# CB_v1.net
KiCad netlist of a schematic drawn in EAGLE
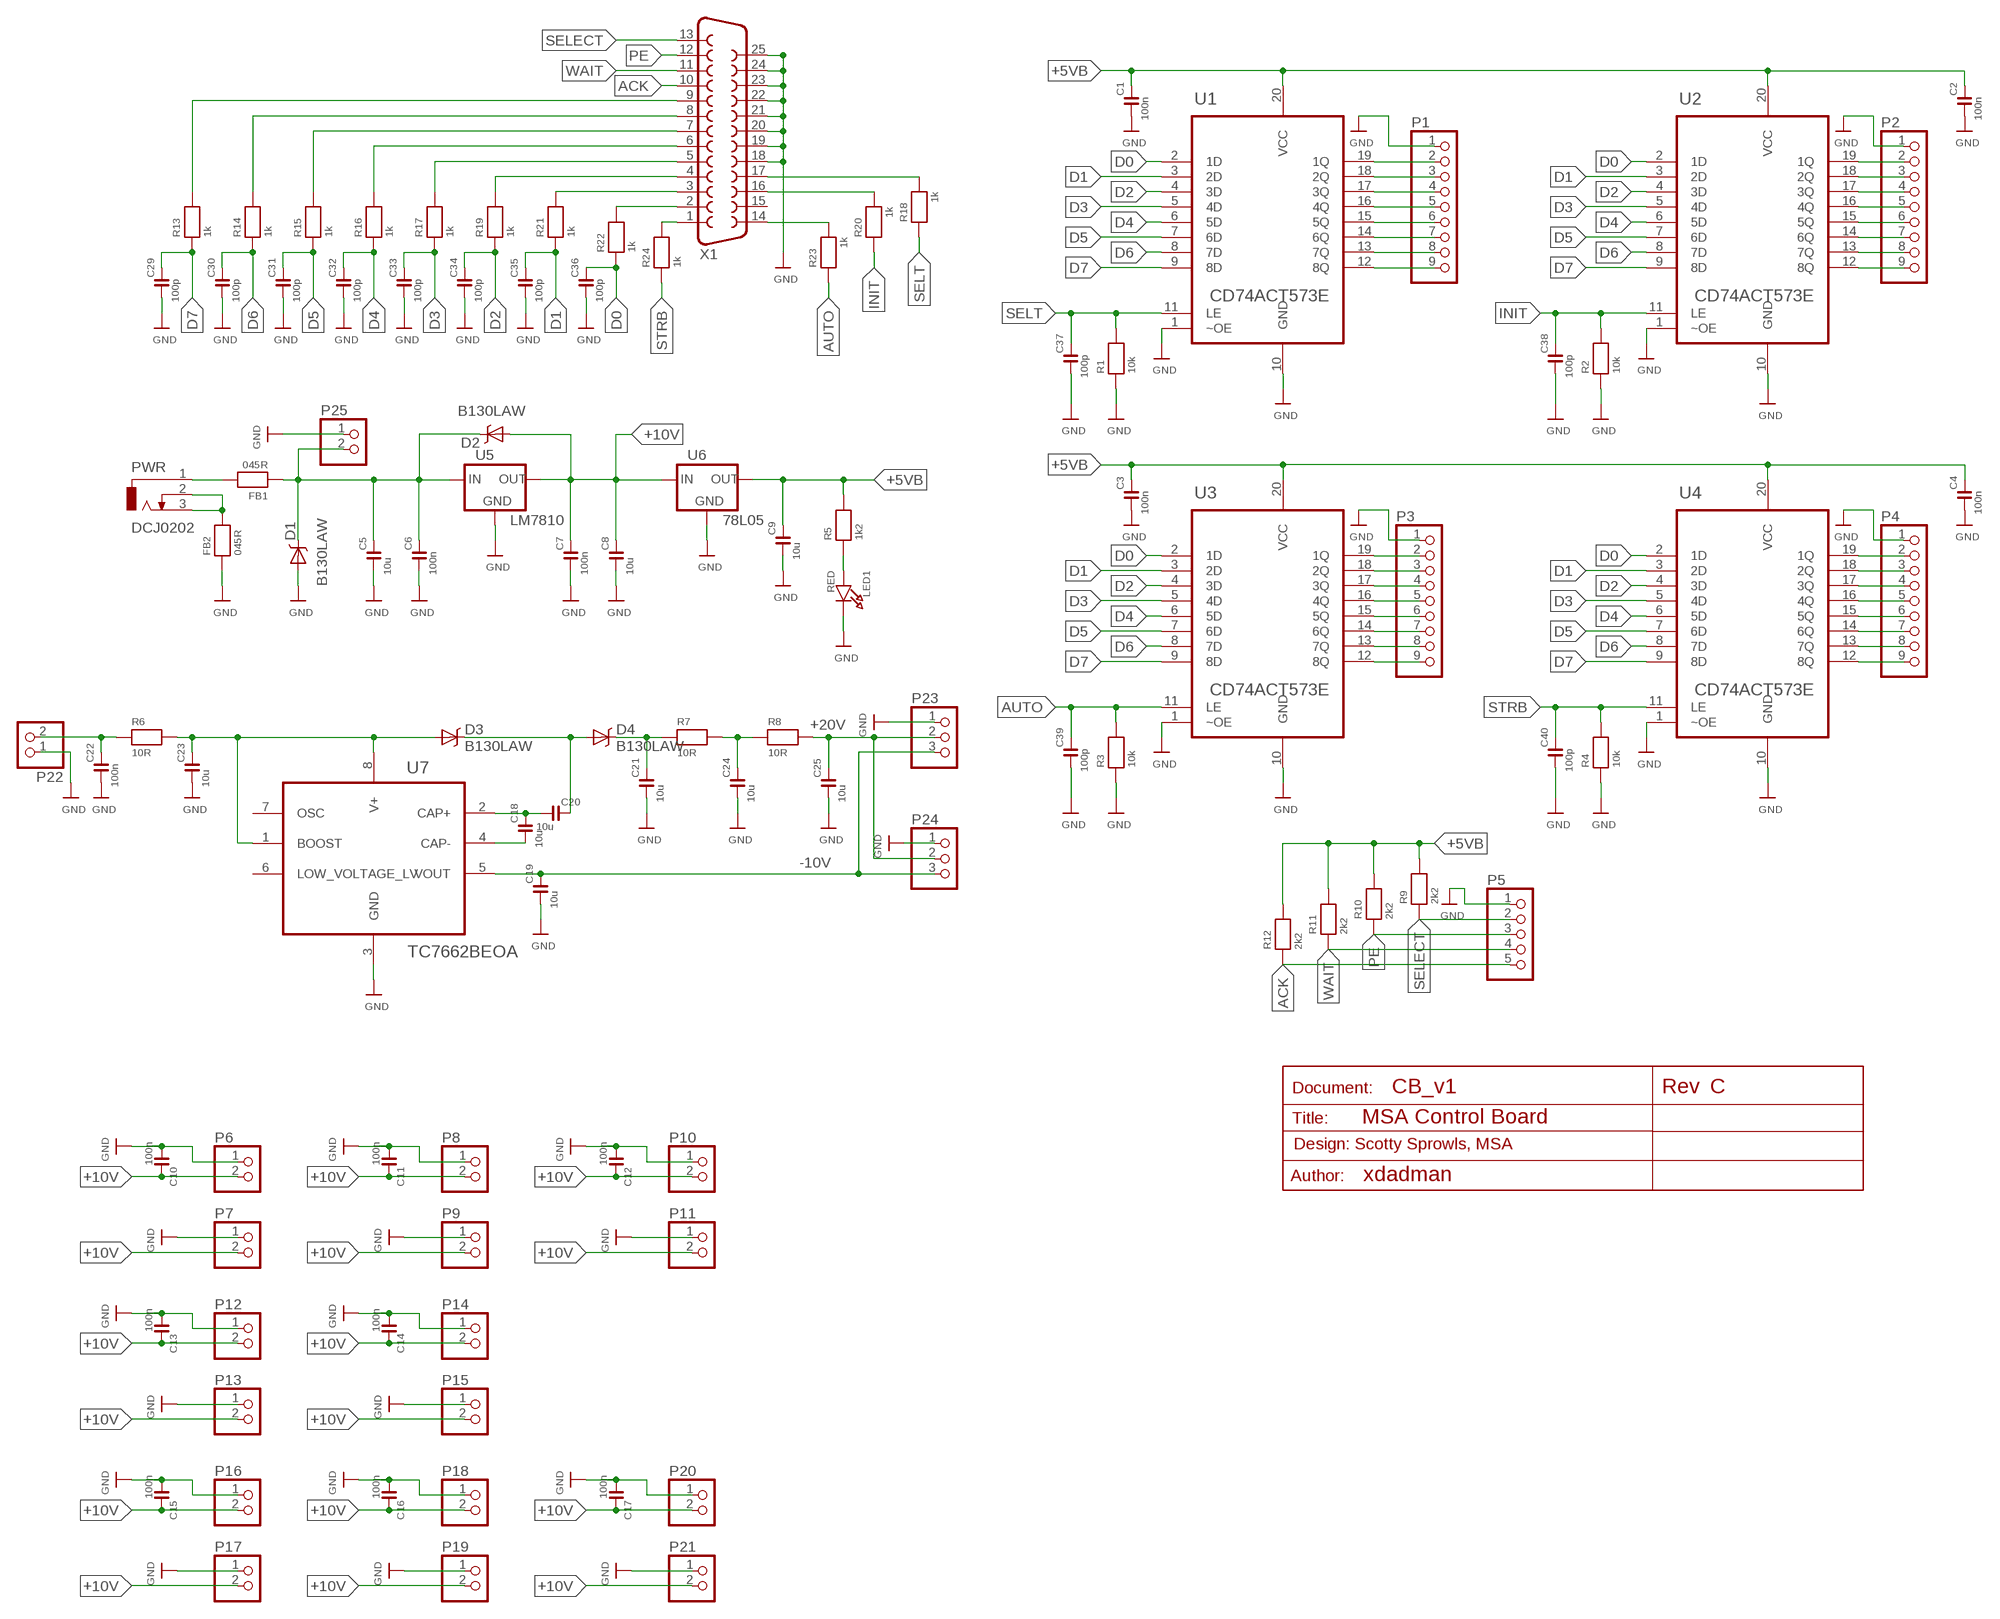
[diagram p0: schematic, sheet 1]

(export (version "E")
  (design (tool "Eeschema 10.0.6"))
  (components
    (comp (ref "C1")
      (value "100n")
      (footprint "eagle-import:C0805")
      (libsource (lib "eagle-import") (part "C0805100N"))
    )
    (comp (ref "C2")
      (value "100n")
      (footprint "eagle-import:C0805")
      (libsource (lib "eagle-import") (part "C0805100N"))
    )
    (comp (ref "C3")
      (value "100n")
      (footprint "eagle-import:C0805")
      (libsource (lib "eagle-import") (part "C0805100N"))
    )
    (comp (ref "C4")
      (value "100n")
      (footprint "eagle-import:C0805")
      (libsource (lib "eagle-import") (part "C0805100N"))
    )
    (comp (ref "C5")
      (value "10u")
      (footprint "eagle-import:C1206")
      (libsource (lib "eagle-import") (part "CC120610U"))
    )
    (comp (ref "C6")
      (value "100n")
      (footprint "eagle-import:C0805")
      (libsource (lib "eagle-import") (part "C0805100N"))
    )
    (comp (ref "C7")
      (value "100n")
      (footprint "eagle-import:C0805")
      (libsource (lib "eagle-import") (part "C0805100N"))
    )
    (comp (ref "C8")
      (value "10u")
      (footprint "eagle-import:C1206")
      (libsource (lib "eagle-import") (part "CC120610U"))
    )
    (comp (ref "C9")
      (value "10u")
      (footprint "eagle-import:C1206")
      (libsource (lib "eagle-import") (part "CC120610U"))
    )
    (comp (ref "C10")
      (value "100n")
      (footprint "eagle-import:C0805")
      (libsource (lib "eagle-import") (part "C0805100N"))
    )
    (comp (ref "C11")
      (value "100n")
      (footprint "eagle-import:C0805")
      (libsource (lib "eagle-import") (part "C0805100N"))
    )
    (comp (ref "C12")
      (value "100n")
      (footprint "eagle-import:C0805")
      (libsource (lib "eagle-import") (part "C0805100N"))
    )
    (comp (ref "C13")
      (value "100n")
      (footprint "eagle-import:C0805")
      (libsource (lib "eagle-import") (part "C0805100N"))
    )
    (comp (ref "C14")
      (value "100n")
      (footprint "eagle-import:C0805")
      (libsource (lib "eagle-import") (part "C0805100N"))
    )
    (comp (ref "C15")
      (value "100n")
      (footprint "eagle-import:C0805")
      (libsource (lib "eagle-import") (part "C0805100N"))
    )
    (comp (ref "C16")
      (value "100n")
      (footprint "eagle-import:C0805")
      (libsource (lib "eagle-import") (part "C0805100N"))
    )
    (comp (ref "C17")
      (value "100n")
      (footprint "eagle-import:C0805")
      (libsource (lib "eagle-import") (part "C0805100N"))
    )
    (comp (ref "C18")
      (value "10u")
      (footprint "eagle-import:C1206")
      (libsource (lib "eagle-import") (part "CC120610U"))
    )
    (comp (ref "C19")
      (value "10u")
      (footprint "eagle-import:C1206")
      (libsource (lib "eagle-import") (part "CC120610U"))
    )
    (comp (ref "C20")
      (value "10u")
      (footprint "eagle-import:C1206")
      (libsource (lib "eagle-import") (part "CC120610U"))
    )
    (comp (ref "C21")
      (value "10u")
      (footprint "eagle-import:C1206")
      (libsource (lib "eagle-import") (part "CC120610U"))
    )
    (comp (ref "C22")
      (value "100n")
      (footprint "eagle-import:C0805")
      (libsource (lib "eagle-import") (part "C0805100N"))
    )
    (comp (ref "C23")
      (value "10u")
      (footprint "eagle-import:C1206")
      (libsource (lib "eagle-import") (part "CC120610U"))
    )
    (comp (ref "C24")
      (value "10u")
      (footprint "eagle-import:C1206")
      (libsource (lib "eagle-import") (part "CC120610U"))
    )
    (comp (ref "C25")
      (value "10u")
      (footprint "eagle-import:C1206")
      (libsource (lib "eagle-import") (part "CC120610U"))
    )
    (comp (ref "C29")
      (value "100p")
      (footprint "eagle-import:C0805")
      (libsource (lib "eagle-import") (part "C0805100P"))
    )
    (comp (ref "C30")
      (value "100p")
      (footprint "eagle-import:C0805")
      (libsource (lib "eagle-import") (part "C0805100P"))
    )
    (comp (ref "C31")
      (value "100p")
      (footprint "eagle-import:C0805")
      (libsource (lib "eagle-import") (part "C0805100P"))
    )
    (comp (ref "C32")
      (value "100p")
      (footprint "eagle-import:C0805")
      (libsource (lib "eagle-import") (part "C0805100P"))
    )
    (comp (ref "C33")
      (value "100p")
      (footprint "eagle-import:C0805")
      (libsource (lib "eagle-import") (part "C0805100P"))
    )
    (comp (ref "C34")
      (value "100p")
      (footprint "eagle-import:C0805")
      (libsource (lib "eagle-import") (part "C0805100P"))
    )
    (comp (ref "C35")
      (value "100p")
      (footprint "eagle-import:C0805")
      (libsource (lib "eagle-import") (part "C0805100P"))
    )
    (comp (ref "C36")
      (value "100p")
      (footprint "eagle-import:C0805")
      (libsource (lib "eagle-import") (part "C0805100P"))
    )
    (comp (ref "C37")
      (value "100p")
      (footprint "eagle-import:C0805")
      (libsource (lib "eagle-import") (part "C0805100P"))
    )
    (comp (ref "C38")
      (value "100p")
      (footprint "eagle-import:C0805")
      (libsource (lib "eagle-import") (part "C0805100P"))
    )
    (comp (ref "C39")
      (value "100p")
      (footprint "eagle-import:C0805")
      (libsource (lib "eagle-import") (part "C0805100P"))
    )
    (comp (ref "C40")
      (value "100p")
      (footprint "eagle-import:C0805")
      (libsource (lib "eagle-import") (part "C0805100P"))
    )
    (comp (ref "D1")
      (value "B130LAW")
      (footprint "eagle-import:SOD-123")
      (libsource (lib "eagle-import") (part "B130LAW-7-FB130LAW-7-F"))
    )
    (comp (ref "D2")
      (value "B130LAW")
      (footprint "eagle-import:SOD-123")
      (libsource (lib "eagle-import") (part "B130LAW-7-FB130LAW-7-F"))
    )
    (comp (ref "D3")
      (value "B130LAW")
      (footprint "eagle-import:SOD-123")
      (libsource (lib "eagle-import") (part "B130LAW-7-FB130LAW-7-F"))
    )
    (comp (ref "D4")
      (value "B130LAW")
      (footprint "eagle-import:SOD-123")
      (libsource (lib "eagle-import") (part "B130LAW-7-FB130LAW-7-F"))
    )
    (comp (ref "FB1")
      (value "045R")
      (footprint "eagle-import:R0805")
      (libsource (lib "eagle-import") (part "R0805FB045"))
    )
    (comp (ref "FB2")
      (value "045R")
      (footprint "eagle-import:R0805")
      (libsource (lib "eagle-import") (part "R0805FB045"))
    )
    (comp (ref "LED1")
      (value "RED")
      (footprint "eagle-import:CHIPLED_0603")
      (libsource (lib "eagle-import") (part "LED_0603_RED0603"))
    )
    (comp (ref "P1")
      (value "PINHD-1X9")
      (footprint "eagle-import:1X09ROUND")
      (libsource (lib "eagle-import") (part "PINHD-1X9"))
    )
    (comp (ref "P2")
      (value "PINHD-1X9")
      (footprint "eagle-import:1X09ROUND")
      (libsource (lib "eagle-import") (part "PINHD-1X9"))
    )
    (comp (ref "P3")
      (value "PINHD-1X9")
      (footprint "eagle-import:1X09ROUND")
      (libsource (lib "eagle-import") (part "PINHD-1X9"))
    )
    (comp (ref "P4")
      (value "PINHD-1X9")
      (footprint "eagle-import:1X09ROUND")
      (libsource (lib "eagle-import") (part "PINHD-1X9"))
    )
    (comp (ref "P5")
      (value "PINHD-1X5")
      (footprint "eagle-import:1X05")
      (libsource (lib "eagle-import") (part "PINHD-1X5"))
    )
    (comp (ref "P6")
      (value "PINHD-1X2")
      (footprint "eagle-import:1X02")
      (libsource (lib "eagle-import") (part "PINHD-1X2"))
    )
    (comp (ref "P7")
      (value "PINHD-1X2")
      (footprint "eagle-import:1X02")
      (libsource (lib "eagle-import") (part "PINHD-1X2"))
    )
    (comp (ref "P8")
      (value "PINHD-1X2")
      (footprint "eagle-import:1X02")
      (libsource (lib "eagle-import") (part "PINHD-1X2"))
    )
    (comp (ref "P9")
      (value "PINHD-1X2")
      (footprint "eagle-import:1X02")
      (libsource (lib "eagle-import") (part "PINHD-1X2"))
    )
    (comp (ref "P10")
      (value "PINHD-1X2")
      (footprint "eagle-import:1X02")
      (libsource (lib "eagle-import") (part "PINHD-1X2"))
    )
    (comp (ref "P11")
      (value "PINHD-1X2")
      (footprint "eagle-import:1X02")
      (libsource (lib "eagle-import") (part "PINHD-1X2"))
    )
    (comp (ref "P12")
      (value "PINHD-1X2")
      (footprint "eagle-import:1X02")
      (libsource (lib "eagle-import") (part "PINHD-1X2"))
    )
    (comp (ref "P13")
      (value "PINHD-1X2")
      (footprint "eagle-import:1X02")
      (libsource (lib "eagle-import") (part "PINHD-1X2"))
    )
    (comp (ref "P14")
      (value "PINHD-1X2")
      (footprint "eagle-import:1X02")
      (libsource (lib "eagle-import") (part "PINHD-1X2"))
    )
    (comp (ref "P15")
      (value "PINHD-1X2")
      (footprint "eagle-import:1X02")
      (libsource (lib "eagle-import") (part "PINHD-1X2"))
    )
    (comp (ref "P16")
      (value "PINHD-1X2")
      (footprint "eagle-import:1X02")
      (libsource (lib "eagle-import") (part "PINHD-1X2"))
    )
    (comp (ref "P17")
      (value "PINHD-1X2")
      (footprint "eagle-import:1X02")
      (libsource (lib "eagle-import") (part "PINHD-1X2"))
    )
    (comp (ref "P18")
      (value "PINHD-1X2")
      (footprint "eagle-import:1X02")
      (libsource (lib "eagle-import") (part "PINHD-1X2"))
    )
    (comp (ref "P19")
      (value "PINHD-1X2")
      (footprint "eagle-import:1X02")
      (libsource (lib "eagle-import") (part "PINHD-1X2"))
    )
    (comp (ref "P20")
      (value "PINHD-1X2")
      (footprint "eagle-import:1X02")
      (libsource (lib "eagle-import") (part "PINHD-1X2"))
    )
    (comp (ref "P21")
      (value "PINHD-1X2")
      (footprint "eagle-import:1X02")
      (libsource (lib "eagle-import") (part "PINHD-1X2"))
    )
    (comp (ref "P22")
      (value "PINHD-1X2")
      (footprint "eagle-import:1X02")
      (libsource (lib "eagle-import") (part "PINHD-1X2"))
    )
    (comp (ref "P23")
      (value "PINHD-1X3")
      (footprint "eagle-import:1X03")
      (libsource (lib "eagle-import") (part "PINHD-1X3"))
    )
    (comp (ref "P24")
      (value "PINHD-1X3")
      (footprint "eagle-import:1X03")
      (libsource (lib "eagle-import") (part "PINHD-1X3"))
    )
    (comp (ref "P25")
      (value "PINHD-1X2")
      (footprint "eagle-import:1X02")
      (libsource (lib "eagle-import") (part "PINHD-1X2"))
    )
    (comp (ref "PWR")
      (value "DCJ0202")
      (footprint "eagle-import:DCJ0202")
      (libsource (lib "eagle-import") (part "DCJ0202"))
    )
    (comp (ref "R1")
      (value "10k")
      (footprint "eagle-import:R0805")
      (libsource (lib "eagle-import") (part "R080510K"))
    )
    (comp (ref "R2")
      (value "10k")
      (footprint "eagle-import:R0805")
      (libsource (lib "eagle-import") (part "R080510K"))
    )
    (comp (ref "R3")
      (value "10k")
      (footprint "eagle-import:R0805")
      (libsource (lib "eagle-import") (part "R080510K"))
    )
    (comp (ref "R4")
      (value "10k")
      (footprint "eagle-import:R0805")
      (libsource (lib "eagle-import") (part "R080510K"))
    )
    (comp (ref "R5")
      (value "1k2")
      (footprint "eagle-import:R0805")
      (libsource (lib "eagle-import") (part "R08051K2"))
    )
    (comp (ref "R6")
      (value "10R")
      (footprint "eagle-import:R0805")
      (libsource (lib "eagle-import") (part "R080510R"))
    )
    (comp (ref "R7")
      (value "10R")
      (footprint "eagle-import:R0805")
      (libsource (lib "eagle-import") (part "R080510R"))
    )
    (comp (ref "R8")
      (value "10R")
      (footprint "eagle-import:R0805")
      (libsource (lib "eagle-import") (part "R080510R"))
    )
    (comp (ref "R9")
      (value "2k2")
      (footprint "eagle-import:R0805")
      (libsource (lib "eagle-import") (part "R08052K2"))
    )
    (comp (ref "R10")
      (value "2k2")
      (footprint "eagle-import:R0805")
      (libsource (lib "eagle-import") (part "R08052K2"))
    )
    (comp (ref "R11")
      (value "2k2")
      (footprint "eagle-import:R0805")
      (libsource (lib "eagle-import") (part "R08052K2"))
    )
    (comp (ref "R12")
      (value "2k2")
      (footprint "eagle-import:R0805")
      (libsource (lib "eagle-import") (part "R08052K2"))
    )
    (comp (ref "R13")
      (value "1k")
      (footprint "eagle-import:R0805")
      (libsource (lib "eagle-import") (part "R08051K"))
    )
    (comp (ref "R14")
      (value "1k")
      (footprint "eagle-import:R0805")
      (libsource (lib "eagle-import") (part "R08051K"))
    )
    (comp (ref "R15")
      (value "1k")
      (footprint "eagle-import:R0805")
      (libsource (lib "eagle-import") (part "R08051K"))
    )
    (comp (ref "R16")
      (value "1k")
      (footprint "eagle-import:R0805")
      (libsource (lib "eagle-import") (part "R08051K"))
    )
    (comp (ref "R17")
      (value "1k")
      (footprint "eagle-import:R0805")
      (libsource (lib "eagle-import") (part "R08051K"))
    )
    (comp (ref "R18")
      (value "1k")
      (footprint "eagle-import:R0805")
      (libsource (lib "eagle-import") (part "R08051K"))
    )
    (comp (ref "R19")
      (value "1k")
      (footprint "eagle-import:R0805")
      (libsource (lib "eagle-import") (part "R08051K"))
    )
    (comp (ref "R20")
      (value "1k")
      (footprint "eagle-import:R0805")
      (libsource (lib "eagle-import") (part "R08051K"))
    )
    (comp (ref "R21")
      (value "1k")
      (footprint "eagle-import:R0805")
      (libsource (lib "eagle-import") (part "R08051K"))
    )
    (comp (ref "R22")
      (value "1k")
      (footprint "eagle-import:R0805")
      (libsource (lib "eagle-import") (part "R08051K"))
    )
    (comp (ref "R23")
      (value "1k")
      (footprint "eagle-import:R0805")
      (libsource (lib "eagle-import") (part "R08051K"))
    )
    (comp (ref "R24")
      (value "1k")
      (footprint "eagle-import:R0805")
      (libsource (lib "eagle-import") (part "R08051K"))
    )
    (comp (ref "U1")
      (value "CD74ACT573E")
      (footprint "eagle-import:DIP254P762X508-20")
      (libsource (lib "eagle-import") (part "CD74ACT573E"))
    )
    (comp (ref "U2")
      (value "CD74ACT573E")
      (footprint "eagle-import:DIP254P762X508-20")
      (libsource (lib "eagle-import") (part "CD74ACT573E"))
    )
    (comp (ref "U3")
      (value "CD74ACT573E")
      (footprint "eagle-import:DIP254P762X508-20")
      (libsource (lib "eagle-import") (part "CD74ACT573E"))
    )
    (comp (ref "U4")
      (value "CD74ACT573E")
      (footprint "eagle-import:DIP254P762X508-20")
      (libsource (lib "eagle-import") (part "CD74ACT573E"))
    )
    (comp (ref "U5")
      (value "LM7810")
      (footprint "eagle-import:TO220V")
      (libsource (lib "eagle-import") (part "78MXXLLM7810"))
    )
    (comp (ref "U6")
      (value "78L05")
      (footprint "eagle-import:SOT89")
      (libsource (lib "eagle-import") (part "78MXXL78L05"))
    )
    (comp (ref "U7")
      (value "TC7662BEOA")
      (footprint "eagle-import:SOIC127P600X175-8N_JDA")
      (libsource (lib "eagle-import") (part "TC7662BEOA"))
    )
    (comp (ref "X1")
      (value "F25D")
      (footprint "eagle-import:F25D")
      (libsource (lib "eagle-import") (part "F25D"))
    )
  )
  (nets
    (net (code "1") (name "+5VB") (class "Default")
      (node (ref "C1") (pin "2") (pinfunction "2_2") (pintype "passive"))
      (node (ref "C2") (pin "2") (pinfunction "2_2") (pintype "passive"))
      (node (ref "C3") (pin "2") (pinfunction "2_2") (pintype "passive"))
      (node (ref "C4") (pin "2") (pinfunction "2_2") (pintype "passive"))
      (node (ref "C9") (pin "2") (pinfunction "2_2") (pintype "passive"))
      (node (ref "R10") (pin "2") (pinfunction "2_2") (pintype "passive"))
      (node (ref "R11") (pin "2") (pinfunction "2_2") (pintype "passive"))
      (node (ref "R12") (pin "2") (pinfunction "2_2") (pintype "passive"))
      (node (ref "R5") (pin "2") (pinfunction "2_2") (pintype "passive"))
      (node (ref "R9") (pin "2") (pinfunction "2_2") (pintype "passive"))
      (node (ref "U1") (pin "20") (pinfunction "VCC_20") (pintype "power_in"))
      (node (ref "U2") (pin "20") (pinfunction "VCC_20") (pintype "power_in"))
      (node (ref "U3") (pin "20") (pinfunction "VCC_20") (pintype "power_in"))
      (node (ref "U4") (pin "20") (pinfunction "VCC_20") (pintype "power_in"))
      (node (ref "U6") (pin "1") (pinfunction "OUT_1") (pintype "passive"))
    )
    (net (code "2") (name "+10V") (class "Default")
      (node (ref "C10") (pin "2") (pinfunction "2_2") (pintype "passive"))
      (node (ref "C11") (pin "2") (pinfunction "2_2") (pintype "passive"))
      (node (ref "C12") (pin "2") (pinfunction "2_2") (pintype "passive"))
      (node (ref "C13") (pin "2") (pinfunction "2_2") (pintype "passive"))
      (node (ref "C14") (pin "2") (pinfunction "2_2") (pintype "passive"))
      (node (ref "C15") (pin "2") (pinfunction "2_2") (pintype "passive"))
      (node (ref "C16") (pin "2") (pinfunction "2_2") (pintype "passive"))
      (node (ref "C17") (pin "2") (pinfunction "2_2") (pintype "passive"))
      (node (ref "C7") (pin "2") (pinfunction "2_2") (pintype "passive"))
      (node (ref "C8") (pin "2") (pinfunction "2_2") (pintype "passive"))
      (node (ref "D2") (pin "A") (pinfunction "A_A") (pintype "passive"))
      (node (ref "P10") (pin "2") (pinfunction "2_2") (pintype "passive"))
      (node (ref "P11") (pin "2") (pinfunction "2_2") (pintype "passive"))
      (node (ref "P12") (pin "2") (pinfunction "2_2") (pintype "passive"))
      (node (ref "P13") (pin "2") (pinfunction "2_2") (pintype "passive"))
      (node (ref "P14") (pin "2") (pinfunction "2_2") (pintype "passive"))
      (node (ref "P15") (pin "2") (pinfunction "2_2") (pintype "passive"))
      (node (ref "P16") (pin "2") (pinfunction "2_2") (pintype "passive"))
      (node (ref "P17") (pin "2") (pinfunction "2_2") (pintype "passive"))
      (node (ref "P18") (pin "2") (pinfunction "2_2") (pintype "passive"))
      (node (ref "P19") (pin "2") (pinfunction "2_2") (pintype "passive"))
      (node (ref "P20") (pin "2") (pinfunction "2_2") (pintype "passive"))
      (node (ref "P21") (pin "2") (pinfunction "2_2") (pintype "passive"))
      (node (ref "P6") (pin "2") (pinfunction "2_2") (pintype "passive"))
      (node (ref "P7") (pin "2") (pinfunction "2_2") (pintype "passive"))
      (node (ref "P8") (pin "2") (pinfunction "2_2") (pintype "passive"))
      (node (ref "P9") (pin "2") (pinfunction "2_2") (pintype "passive"))
      (node (ref "U5") (pin "3") (pinfunction "OUT_3") (pintype "passive"))
      (node (ref "U6") (pin "3") (pinfunction "IN_3") (pintype "input"))
    )
    (net (code "3") (name "/+20V") (class "Default")
      (node (ref "C25") (pin "2") (pinfunction "2_2") (pintype "passive"))
      (node (ref "P23") (pin "2") (pinfunction "2_2") (pintype "passive"))
      (node (ref "P24") (pin "2") (pinfunction "2_2") (pintype "passive"))
      (node (ref "R8") (pin "2") (pinfunction "2_2") (pintype "passive"))
    )
    (net (code "4") (name "/-10V") (class "Default")
      (node (ref "C19") (pin "2") (pinfunction "2_2") (pintype "passive"))
      (node (ref "P23") (pin "3") (pinfunction "3_3") (pintype "passive"))
      (node (ref "P24") (pin "3") (pinfunction "3_3") (pintype "passive"))
      (node (ref "U7") (pin "5") (pinfunction "VOUT_5") (pintype "output"))
    )
    (net (code "5") (name "ACK") (class "Default")
      (node (ref "P5") (pin "5") (pinfunction "5_5") (pintype "passive"))
      (node (ref "R12") (pin "1") (pinfunction "1_1") (pintype "passive"))
      (node (ref "X1") (pin "10") (pinfunction "10_10") (pintype "passive"))
    )
    (net (code "6") (name "AUTO") (class "Default")
      (node (ref "C39") (pin "2") (pinfunction "2_2") (pintype "passive"))
      (node (ref "R23") (pin "2") (pinfunction "2_2") (pintype "passive"))
      (node (ref "R3") (pin "2") (pinfunction "2_2") (pintype "passive"))
      (node (ref "U3") (pin "11") (pinfunction "LE_11") (pintype "input"))
    )
    (net (code "7") (name "D0") (class "Default")
      (node (ref "C36") (pin "2") (pinfunction "2_2") (pintype "passive"))
      (node (ref "R22") (pin "1") (pinfunction "1_1") (pintype "passive"))
      (node (ref "U1") (pin "2") (pinfunction "1D_2") (pintype "input"))
      (node (ref "U2") (pin "2") (pinfunction "1D_2") (pintype "input"))
      (node (ref "U3") (pin "2") (pinfunction "1D_2") (pintype "input"))
      (node (ref "U4") (pin "2") (pinfunction "1D_2") (pintype "input"))
    )
    (net (code "8") (name "D1") (class "Default")
      (node (ref "C35") (pin "2") (pinfunction "2_2") (pintype "passive"))
      (node (ref "R21") (pin "1") (pinfunction "1_1") (pintype "passive"))
      (node (ref "U1") (pin "3") (pinfunction "2D_3") (pintype "input"))
      (node (ref "U2") (pin "3") (pinfunction "2D_3") (pintype "input"))
      (node (ref "U3") (pin "3") (pinfunction "2D_3") (pintype "input"))
      (node (ref "U4") (pin "3") (pinfunction "2D_3") (pintype "input"))
    )
    (net (code "9") (name "D2") (class "Default")
      (node (ref "C34") (pin "2") (pinfunction "2_2") (pintype "passive"))
      (node (ref "R19") (pin "1") (pinfunction "1_1") (pintype "passive"))
      (node (ref "U1") (pin "4") (pinfunction "3D_4") (pintype "input"))
      (node (ref "U2") (pin "4") (pinfunction "3D_4") (pintype "input"))
      (node (ref "U3") (pin "4") (pinfunction "3D_4") (pintype "input"))
      (node (ref "U4") (pin "4") (pinfunction "3D_4") (pintype "input"))
    )
    (net (code "10") (name "D3") (class "Default")
      (node (ref "C33") (pin "2") (pinfunction "2_2") (pintype "passive"))
      (node (ref "R17") (pin "1") (pinfunction "1_1") (pintype "passive"))
      (node (ref "U1") (pin "5") (pinfunction "4D_5") (pintype "input"))
      (node (ref "U2") (pin "5") (pinfunction "4D_5") (pintype "input"))
      (node (ref "U3") (pin "5") (pinfunction "4D_5") (pintype "input"))
      (node (ref "U4") (pin "5") (pinfunction "4D_5") (pintype "input"))
    )
    (net (code "11") (name "D4") (class "Default")
      (node (ref "C32") (pin "2") (pinfunction "2_2") (pintype "passive"))
      (node (ref "R16") (pin "1") (pinfunction "1_1") (pintype "passive"))
      (node (ref "U1") (pin "6") (pinfunction "5D_6") (pintype "input"))
      (node (ref "U2") (pin "6") (pinfunction "5D_6") (pintype "input"))
      (node (ref "U3") (pin "6") (pinfunction "5D_6") (pintype "input"))
      (node (ref "U4") (pin "6") (pinfunction "5D_6") (pintype "input"))
    )
    (net (code "12") (name "D5") (class "Default")
      (node (ref "C31") (pin "2") (pinfunction "2_2") (pintype "passive"))
      (node (ref "R15") (pin "1") (pinfunction "1_1") (pintype "passive"))
      (node (ref "U1") (pin "7") (pinfunction "6D_7") (pintype "input"))
      (node (ref "U2") (pin "7") (pinfunction "6D_7") (pintype "input"))
      (node (ref "U3") (pin "7") (pinfunction "6D_7") (pintype "input"))
      (node (ref "U4") (pin "7") (pinfunction "6D_7") (pintype "input"))
    )
    (net (code "13") (name "D6") (class "Default")
      (node (ref "C30") (pin "2") (pinfunction "2_2") (pintype "passive"))
      (node (ref "R14") (pin "1") (pinfunction "1_1") (pintype "passive"))
      (node (ref "U1") (pin "8") (pinfunction "7D_8") (pintype "input"))
      (node (ref "U2") (pin "8") (pinfunction "7D_8") (pintype "input"))
      (node (ref "U3") (pin "8") (pinfunction "7D_8") (pintype "input"))
      (node (ref "U4") (pin "8") (pinfunction "7D_8") (pintype "input"))
    )
    (net (code "14") (name "D7") (class "Default")
      (node (ref "C29") (pin "2") (pinfunction "2_2") (pintype "passive"))
      (node (ref "R13") (pin "1") (pinfunction "1_1") (pintype "passive"))
      (node (ref "U1") (pin "9") (pinfunction "8D_9") (pintype "input"))
      (node (ref "U2") (pin "9") (pinfunction "8D_9") (pintype "input"))
      (node (ref "U3") (pin "9") (pinfunction "8D_9") (pintype "input"))
      (node (ref "U4") (pin "9") (pinfunction "8D_9") (pintype "input"))
    )
    (net (code "15") (name "GND") (class "Default")
      (node (ref "C1") (pin "1") (pinfunction "1_1") (pintype "passive"))
      (node (ref "C10") (pin "1") (pinfunction "1_1") (pintype "passive"))
      (node (ref "C11") (pin "1") (pinfunction "1_1") (pintype "passive"))
      (node (ref "C12") (pin "1") (pinfunction "1_1") (pintype "passive"))
      (node (ref "C13") (pin "1") (pinfunction "1_1") (pintype "passive"))
      (node (ref "C14") (pin "1") (pinfunction "1_1") (pintype "passive"))
      (node (ref "C15") (pin "1") (pinfunction "1_1") (pintype "passive"))
      (node (ref "C16") (pin "1") (pinfunction "1_1") (pintype "passive"))
      (node (ref "C17") (pin "1") (pinfunction "1_1") (pintype "passive"))
      (node (ref "C19") (pin "1") (pinfunction "1_1") (pintype "passive"))
      (node (ref "C2") (pin "1") (pinfunction "1_1") (pintype "passive"))
      (node (ref "C21") (pin "1") (pinfunction "1_1") (pintype "passive"))
      (node (ref "C22") (pin "1") (pinfunction "1_1") (pintype "passive"))
      (node (ref "C23") (pin "1") (pinfunction "1_1") (pintype "passive"))
      (node (ref "C24") (pin "1") (pinfunction "1_1") (pintype "passive"))
      (node (ref "C25") (pin "1") (pinfunction "1_1") (pintype "passive"))
      (node (ref "C29") (pin "1") (pinfunction "1_1") (pintype "passive"))
      (node (ref "C3") (pin "1") (pinfunction "1_1") (pintype "passive"))
      (node (ref "C30") (pin "1") (pinfunction "1_1") (pintype "passive"))
      (node (ref "C31") (pin "1") (pinfunction "1_1") (pintype "passive"))
      (node (ref "C32") (pin "1") (pinfunction "1_1") (pintype "passive"))
      (node (ref "C33") (pin "1") (pinfunction "1_1") (pintype "passive"))
      (node (ref "C34") (pin "1") (pinfunction "1_1") (pintype "passive"))
      (node (ref "C35") (pin "1") (pinfunction "1_1") (pintype "passive"))
      (node (ref "C36") (pin "1") (pinfunction "1_1") (pintype "passive"))
      (node (ref "C37") (pin "1") (pinfunction "1_1") (pintype "passive"))
      (node (ref "C38") (pin "1") (pinfunction "1_1") (pintype "passive"))
      (node (ref "C39") (pin "1") (pinfunction "1_1") (pintype "passive"))
      (node (ref "C4") (pin "1") (pinfunction "1_1") (pintype "passive"))
      (node (ref "C40") (pin "1") (pinfunction "1_1") (pintype "passive"))
      (node (ref "C5") (pin "1") (pinfunction "1_1") (pintype "passive"))
      (node (ref "C6") (pin "1") (pinfunction "1_1") (pintype "passive"))
      (node (ref "C7") (pin "1") (pinfunction "1_1") (pintype "passive"))
      (node (ref "C8") (pin "1") (pinfunction "1_1") (pintype "passive"))
      (node (ref "C9") (pin "1") (pinfunction "1_1") (pintype "passive"))
      (node (ref "D1") (pin "A") (pinfunction "A_A") (pintype "passive"))
      (node (ref "FB2") (pin "1") (pinfunction "1_1") (pintype "passive"))
      (node (ref "LED1") (pin "C") (pinfunction "C_C") (pintype "passive"))
      (node (ref "P1") (pin "1") (pinfunction "1_1") (pintype "passive"))
      (node (ref "P10") (pin "1") (pinfunction "1_1") (pintype "passive"))
      (node (ref "P11") (pin "1") (pinfunction "1_1") (pintype "passive"))
      (node (ref "P12") (pin "1") (pinfunction "1_1") (pintype "passive"))
      (node (ref "P13") (pin "1") (pinfunction "1_1") (pintype "passive"))
      (node (ref "P14") (pin "1") (pinfunction "1_1") (pintype "passive"))
      (node (ref "P15") (pin "1") (pinfunction "1_1") (pintype "passive"))
      (node (ref "P16") (pin "1") (pinfunction "1_1") (pintype "passive"))
      (node (ref "P17") (pin "1") (pinfunction "1_1") (pintype "passive"))
      (node (ref "P18") (pin "1") (pinfunction "1_1") (pintype "passive"))
      (node (ref "P19") (pin "1") (pinfunction "1_1") (pintype "passive"))
      (node (ref "P2") (pin "1") (pinfunction "1_1") (pintype "passive"))
      (node (ref "P20") (pin "1") (pinfunction "1_1") (pintype "passive"))
      (node (ref "P21") (pin "1") (pinfunction "1_1") (pintype "passive"))
      (node (ref "P22") (pin "1") (pinfunction "1_1") (pintype "passive"))
      (node (ref "P23") (pin "1") (pinfunction "1_1") (pintype "passive"))
      (node (ref "P24") (pin "1") (pinfunction "1_1") (pintype "passive"))
      (node (ref "P25") (pin "1") (pinfunction "1_1") (pintype "passive"))
      (node (ref "P3") (pin "1") (pinfunction "1_1") (pintype "passive"))
      (node (ref "P4") (pin "1") (pinfunction "1_1") (pintype "passive"))
      (node (ref "P5") (pin "1") (pinfunction "1_1") (pintype "passive"))
      (node (ref "P6") (pin "1") (pinfunction "1_1") (pintype "passive"))
      (node (ref "P7") (pin "1") (pinfunction "1_1") (pintype "passive"))
      (node (ref "P8") (pin "1") (pinfunction "1_1") (pintype "passive"))
      (node (ref "P9") (pin "1") (pinfunction "1_1") (pintype "passive"))
      (node (ref "R1") (pin "1") (pinfunction "1_1") (pintype "passive"))
      (node (ref "R2") (pin "1") (pinfunction "1_1") (pintype "passive"))
      (node (ref "R3") (pin "1") (pinfunction "1_1") (pintype "passive"))
      (node (ref "R4") (pin "1") (pinfunction "1_1") (pintype "passive"))
      (node (ref "U1") (pin "1") (pinfunction "~{OE}_1") (pintype "input"))
      (node (ref "U1") (pin "10") (pinfunction "GND_10") (pintype "passive"))
      (node (ref "U2") (pin "1") (pinfunction "~{OE}_1") (pintype "input"))
      (node (ref "U2") (pin "10") (pinfunction "GND_10") (pintype "passive"))
      (node (ref "U3") (pin "1") (pinfunction "~{OE}_1") (pintype "input"))
      (node (ref "U3") (pin "10") (pinfunction "GND_10") (pintype "passive"))
      (node (ref "U4") (pin "1") (pinfunction "~{OE}_1") (pintype "input"))
      (node (ref "U4") (pin "10") (pinfunction "GND_10") (pintype "passive"))
      (node (ref "U5") (pin "2") (pinfunction "GND_2") (pintype "input"))
      (node (ref "U6") (pin "2") (pinfunction "GND_2") (pintype "input"))
      (node (ref "U6") (pin "4") (pinfunction "GND_4") (pintype "input"))
      (node (ref "U7") (pin "3") (pinfunction "GND_3") (pintype "passive"))
      (node (ref "X1") (pin "18") (pinfunction "18_18") (pintype "passive"))
      (node (ref "X1") (pin "19") (pinfunction "19_19") (pintype "passive"))
      (node (ref "X1") (pin "20") (pinfunction "20_20") (pintype "passive"))
      (node (ref "X1") (pin "21") (pinfunction "21_21") (pintype "passive"))
      (node (ref "X1") (pin "22") (pinfunction "22_22") (pintype "passive"))
      (node (ref "X1") (pin "23") (pinfunction "23_23") (pintype "passive"))
      (node (ref "X1") (pin "24") (pinfunction "24_24") (pintype "passive"))
      (node (ref "X1") (pin "25") (pinfunction "25_25") (pintype "passive"))
    )
    (net (code "16") (name "INIT") (class "Default")
      (node (ref "C38") (pin "2") (pinfunction "2_2") (pintype "passive"))
      (node (ref "R2") (pin "2") (pinfunction "2_2") (pintype "passive"))
      (node (ref "R20") (pin "2") (pinfunction "2_2") (pintype "passive"))
      (node (ref "U2") (pin "11") (pinfunction "LE_11") (pintype "input"))
    )
    (net (code "17") (name "Net-(C20-Pad2)") (class "Default")
      (node (ref "C20") (pin "2") (pinfunction "2_2") (pintype "passive"))
      (node (ref "D3") (pin "C") (pinfunction "C_C") (pintype "passive"))
      (node (ref "D4") (pin "A") (pinfunction "A_A") (pintype "passive"))
    )
    (net (code "18") (name "Net-(C21-Pad2)") (class "Default")
      (node (ref "C21") (pin "2") (pinfunction "2_2") (pintype "passive"))
      (node (ref "D4") (pin "C") (pinfunction "C_C") (pintype "passive"))
      (node (ref "R7") (pin "1") (pinfunction "1_1") (pintype "passive"))
    )
    (net (code "19") (name "Net-(C22-Pad2)") (class "Default")
      (node (ref "C22") (pin "2") (pinfunction "2_2") (pintype "passive"))
      (node (ref "P22") (pin "2") (pinfunction "2_2") (pintype "passive"))
      (node (ref "R6") (pin "1") (pinfunction "1_1") (pintype "passive"))
    )
    (net (code "20") (name "Net-(C24-Pad2)") (class "Default")
      (node (ref "C24") (pin "2") (pinfunction "2_2") (pintype "passive"))
      (node (ref "R7") (pin "2") (pinfunction "2_2") (pintype "passive"))
      (node (ref "R8") (pin "1") (pinfunction "1_1") (pintype "passive"))
    )
    (net (code "21") (name "Net-(FB1-Pad2)") (class "Default")
      (node (ref "FB1") (pin "2") (pinfunction "2_2") (pintype "passive"))
      (node (ref "PWR") (pin "1") (pinfunction "1_1") (pintype "passive"))
    )
    (net (code "22") (name "Net-(FB2-Pad2)") (class "Default")
      (node (ref "FB2") (pin "2") (pinfunction "2_2") (pintype "passive"))
      (node (ref "PWR") (pin "2") (pinfunction "2_2") (pintype "passive"))
      (node (ref "PWR") (pin "3") (pinfunction "3_3") (pintype "passive"))
    )
    (net (code "23") (name "Net-(LED1-PadA)") (class "Default")
      (node (ref "LED1") (pin "A") (pinfunction "A_A") (pintype "passive"))
      (node (ref "R5") (pin "1") (pinfunction "1_1") (pintype "passive"))
    )
    (net (code "24") (name "Net-(R13-Pad2)") (class "Default")
      (node (ref "R13") (pin "2") (pinfunction "2_2") (pintype "passive"))
      (node (ref "X1") (pin "9") (pinfunction "9_9") (pintype "passive"))
    )
    (net (code "25") (name "Net-(R14-Pad2)") (class "Default")
      (node (ref "R14") (pin "2") (pinfunction "2_2") (pintype "passive"))
      (node (ref "X1") (pin "8") (pinfunction "8_8") (pintype "passive"))
    )
    (net (code "26") (name "Net-(R15-Pad2)") (class "Default")
      (node (ref "R15") (pin "2") (pinfunction "2_2") (pintype "passive"))
      (node (ref "X1") (pin "7") (pinfunction "7_7") (pintype "passive"))
    )
    (net (code "27") (name "Net-(R16-Pad2)") (class "Default")
      (node (ref "R16") (pin "2") (pinfunction "2_2") (pintype "passive"))
      (node (ref "X1") (pin "6") (pinfunction "6_6") (pintype "passive"))
    )
    (net (code "28") (name "Net-(R17-Pad2)") (class "Default")
      (node (ref "R17") (pin "2") (pinfunction "2_2") (pintype "passive"))
      (node (ref "X1") (pin "5") (pinfunction "5_5") (pintype "passive"))
    )
    (net (code "29") (name "Net-(R18-Pad1)") (class "Default")
      (node (ref "R18") (pin "1") (pinfunction "1_1") (pintype "passive"))
      (node (ref "X1") (pin "17") (pinfunction "17_17") (pintype "passive"))
    )
    (net (code "30") (name "Net-(R19-Pad2)") (class "Default")
      (node (ref "R19") (pin "2") (pinfunction "2_2") (pintype "passive"))
      (node (ref "X1") (pin "4") (pinfunction "4_4") (pintype "passive"))
    )
    (net (code "31") (name "Net-(R20-Pad1)") (class "Default")
      (node (ref "R20") (pin "1") (pinfunction "1_1") (pintype "passive"))
      (node (ref "X1") (pin "16") (pinfunction "16_16") (pintype "passive"))
    )
    (net (code "32") (name "Net-(R21-Pad2)") (class "Default")
      (node (ref "R21") (pin "2") (pinfunction "2_2") (pintype "passive"))
      (node (ref "X1") (pin "3") (pinfunction "3_3") (pintype "passive"))
    )
    (net (code "33") (name "Net-(R22-Pad2)") (class "Default")
      (node (ref "R22") (pin "2") (pinfunction "2_2") (pintype "passive"))
      (node (ref "X1") (pin "2") (pinfunction "2_2") (pintype "passive"))
    )
    (net (code "34") (name "Net-(R23-Pad1)") (class "Default")
      (node (ref "R23") (pin "1") (pinfunction "1_1") (pintype "passive"))
      (node (ref "X1") (pin "14") (pinfunction "14_14") (pintype "passive"))
    )
    (net (code "35") (name "Net-(R24-Pad2)") (class "Default")
      (node (ref "R24") (pin "2") (pinfunction "2_2") (pintype "passive"))
      (node (ref "X1") (pin "1") (pinfunction "1_1") (pintype "passive"))
    )
    (net (code "36") (name "Net-(U1-1Q)") (class "Default")
      (node (ref "P1") (pin "2") (pinfunction "2_2") (pintype "passive"))
      (node (ref "U1") (pin "19") (pinfunction "1Q_19") (pintype "output"))
    )
    (net (code "37") (name "Net-(U1-2Q)") (class "Default")
      (node (ref "P1") (pin "3") (pinfunction "3_3") (pintype "passive"))
      (node (ref "U1") (pin "18") (pinfunction "2Q_18") (pintype "output"))
    )
    (net (code "38") (name "Net-(U1-3Q)") (class "Default")
      (node (ref "P1") (pin "4") (pinfunction "4_4") (pintype "passive"))
      (node (ref "U1") (pin "17") (pinfunction "3Q_17") (pintype "output"))
    )
    (net (code "39") (name "Net-(U1-4Q)") (class "Default")
      (node (ref "P1") (pin "5") (pinfunction "5_5") (pintype "passive"))
      (node (ref "U1") (pin "16") (pinfunction "4Q_16") (pintype "output"))
    )
    (net (code "40") (name "Net-(U1-5Q)") (class "Default")
      (node (ref "P1") (pin "6") (pinfunction "6_6") (pintype "passive"))
      (node (ref "U1") (pin "15") (pinfunction "5Q_15") (pintype "output"))
    )
    (net (code "41") (name "Net-(U1-6Q)") (class "Default")
      (node (ref "P1") (pin "7") (pinfunction "7_7") (pintype "passive"))
      (node (ref "U1") (pin "14") (pinfunction "6Q_14") (pintype "output"))
    )
    (net (code "42") (name "Net-(U1-7Q)") (class "Default")
      (node (ref "P1") (pin "8") (pinfunction "8_8") (pintype "passive"))
      (node (ref "U1") (pin "13") (pinfunction "7Q_13") (pintype "output"))
    )
    (net (code "43") (name "Net-(U1-8Q)") (class "Default")
      (node (ref "P1") (pin "9") (pinfunction "9_9") (pintype "passive"))
      (node (ref "U1") (pin "12") (pinfunction "8Q_12") (pintype "output"))
    )
    (net (code "44") (name "Net-(U2-1Q)") (class "Default")
      (node (ref "P2") (pin "2") (pinfunction "2_2") (pintype "passive"))
      (node (ref "U2") (pin "19") (pinfunction "1Q_19") (pintype "output"))
    )
    (net (code "45") (name "Net-(U2-2Q)") (class "Default")
      (node (ref "P2") (pin "3") (pinfunction "3_3") (pintype "passive"))
      (node (ref "U2") (pin "18") (pinfunction "2Q_18") (pintype "output"))
    )
    (net (code "46") (name "Net-(U2-3Q)") (class "Default")
      (node (ref "P2") (pin "4") (pinfunction "4_4") (pintype "passive"))
      (node (ref "U2") (pin "17") (pinfunction "3Q_17") (pintype "output"))
    )
    (net (code "47") (name "Net-(U2-4Q)") (class "Default")
      (node (ref "P2") (pin "5") (pinfunction "5_5") (pintype "passive"))
      (node (ref "U2") (pin "16") (pinfunction "4Q_16") (pintype "output"))
    )
    (net (code "48") (name "Net-(U2-5Q)") (class "Default")
      (node (ref "P2") (pin "6") (pinfunction "6_6") (pintype "passive"))
      (node (ref "U2") (pin "15") (pinfunction "5Q_15") (pintype "output"))
    )
    (net (code "49") (name "Net-(U2-6Q)") (class "Default")
      (node (ref "P2") (pin "7") (pinfunction "7_7") (pintype "passive"))
      (node (ref "U2") (pin "14") (pinfunction "6Q_14") (pintype "output"))
    )
    (net (code "50") (name "Net-(U2-7Q)") (class "Default")
      (node (ref "P2") (pin "8") (pinfunction "8_8") (pintype "passive"))
      (node (ref "U2") (pin "13") (pinfunction "7Q_13") (pintype "output"))
    )
    (net (code "51") (name "Net-(U2-8Q)") (class "Default")
      (node (ref "P2") (pin "9") (pinfunction "9_9") (pintype "passive"))
      (node (ref "U2") (pin "12") (pinfunction "8Q_12") (pintype "output"))
    )
    (net (code "52") (name "Net-(U3-1Q)") (class "Default")
      (node (ref "P3") (pin "2") (pinfunction "2_2") (pintype "passive"))
      (node (ref "U3") (pin "19") (pinfunction "1Q_19") (pintype "output"))
    )
    (net (code "53") (name "Net-(U3-2Q)") (class "Default")
      (node (ref "P3") (pin "3") (pinfunction "3_3") (pintype "passive"))
      (node (ref "U3") (pin "18") (pinfunction "2Q_18") (pintype "output"))
    )
    (net (code "54") (name "Net-(U3-3Q)") (class "Default")
      (node (ref "P3") (pin "4") (pinfunction "4_4") (pintype "passive"))
      (node (ref "U3") (pin "17") (pinfunction "3Q_17") (pintype "output"))
    )
    (net (code "55") (name "Net-(U3-4Q)") (class "Default")
      (node (ref "P3") (pin "5") (pinfunction "5_5") (pintype "passive"))
      (node (ref "U3") (pin "16") (pinfunction "4Q_16") (pintype "output"))
    )
    (net (code "56") (name "Net-(U3-5Q)") (class "Default")
      (node (ref "P3") (pin "6") (pinfunction "6_6") (pintype "passive"))
      (node (ref "U3") (pin "15") (pinfunction "5Q_15") (pintype "output"))
    )
    (net (code "57") (name "Net-(U3-6Q)") (class "Default")
      (node (ref "P3") (pin "7") (pinfunction "7_7") (pintype "passive"))
      (node (ref "U3") (pin "14") (pinfunction "6Q_14") (pintype "output"))
    )
    (net (code "58") (name "Net-(U3-7Q)") (class "Default")
      (node (ref "P3") (pin "8") (pinfunction "8_8") (pintype "passive"))
      (node (ref "U3") (pin "13") (pinfunction "7Q_13") (pintype "output"))
    )
    (net (code "59") (name "Net-(U3-8Q)") (class "Default")
      (node (ref "P3") (pin "9") (pinfunction "9_9") (pintype "passive"))
      (node (ref "U3") (pin "12") (pinfunction "8Q_12") (pintype "output"))
    )
    (net (code "60") (name "Net-(U4-1Q)") (class "Default")
      (node (ref "P4") (pin "2") (pinfunction "2_2") (pintype "passive"))
      (node (ref "U4") (pin "19") (pinfunction "1Q_19") (pintype "output"))
    )
    (net (code "61") (name "Net-(U4-2Q)") (class "Default")
      (node (ref "P4") (pin "3") (pinfunction "3_3") (pintype "passive"))
      (node (ref "U4") (pin "18") (pinfunction "2Q_18") (pintype "output"))
    )
    (net (code "62") (name "Net-(U4-3Q)") (class "Default")
      (node (ref "P4") (pin "4") (pinfunction "4_4") (pintype "passive"))
      (node (ref "U4") (pin "17") (pinfunction "3Q_17") (pintype "output"))
    )
    (net (code "63") (name "Net-(U4-4Q)") (class "Default")
      (node (ref "P4") (pin "5") (pinfunction "5_5") (pintype "passive"))
      (node (ref "U4") (pin "16") (pinfunction "4Q_16") (pintype "output"))
    )
    (net (code "64") (name "Net-(U4-5Q)") (class "Default")
      (node (ref "P4") (pin "6") (pinfunction "6_6") (pintype "passive"))
      (node (ref "U4") (pin "15") (pinfunction "5Q_15") (pintype "output"))
    )
    (net (code "65") (name "Net-(U4-6Q)") (class "Default")
      (node (ref "P4") (pin "7") (pinfunction "7_7") (pintype "passive"))
      (node (ref "U4") (pin "14") (pinfunction "6Q_14") (pintype "output"))
    )
    (net (code "66") (name "Net-(U4-7Q)") (class "Default")
      (node (ref "P4") (pin "8") (pinfunction "8_8") (pintype "passive"))
      (node (ref "U4") (pin "13") (pinfunction "7Q_13") (pintype "output"))
    )
    (net (code "67") (name "Net-(U4-8Q)") (class "Default")
      (node (ref "P4") (pin "9") (pinfunction "9_9") (pintype "passive"))
      (node (ref "U4") (pin "12") (pinfunction "8Q_12") (pintype "output"))
    )
    (net (code "68") (name "Net-(U5-IN)") (class "Default")
      (node (ref "C5") (pin "2") (pinfunction "2_2") (pintype "passive"))
      (node (ref "C6") (pin "2") (pinfunction "2_2") (pintype "passive"))
      (node (ref "D1") (pin "C") (pinfunction "C_C") (pintype "passive"))
      (node (ref "D2") (pin "C") (pinfunction "C_C") (pintype "passive"))
      (node (ref "FB1") (pin "1") (pinfunction "1_1") (pintype "passive"))
      (node (ref "P25") (pin "2") (pinfunction "2_2") (pintype "passive"))
      (node (ref "U5") (pin "1") (pinfunction "IN_1") (pintype "input"))
    )
    (net (code "69") (name "Net-(U7-BOOST)") (class "Default")
      (node (ref "C23") (pin "2") (pinfunction "2_2") (pintype "passive"))
      (node (ref "D3") (pin "A") (pinfunction "A_A") (pintype "passive"))
      (node (ref "R6") (pin "2") (pinfunction "2_2") (pintype "passive"))
      (node (ref "U7") (pin "1") (pinfunction "BOOST_1") (pintype "input"))
      (node (ref "U7") (pin "8") (pinfunction "V+_8") (pintype "power_in"))
    )
    (net (code "70") (name "Net-(U7-CAP+)") (class "Default")
      (node (ref "C18") (pin "2") (pinfunction "2_2") (pintype "passive"))
      (node (ref "C20") (pin "1") (pinfunction "1_1") (pintype "passive"))
      (node (ref "U7") (pin "2") (pinfunction "CAP+_2") (pintype "passive"))
    )
    (net (code "71") (name "Net-(U7-CAP-)") (class "Default")
      (node (ref "C18") (pin "1") (pinfunction "1_1") (pintype "passive"))
      (node (ref "U7") (pin "4") (pinfunction "CAP-_4") (pintype "passive"))
    )
    (net (code "72") (name "PE") (class "Default")
      (node (ref "P5") (pin "3") (pinfunction "3_3") (pintype "passive"))
      (node (ref "R10") (pin "1") (pinfunction "1_1") (pintype "passive"))
      (node (ref "X1") (pin "12") (pinfunction "12_12") (pintype "passive"))
    )
    (net (code "73") (name "SELECT") (class "Default")
      (node (ref "P5") (pin "2") (pinfunction "2_2") (pintype "passive"))
      (node (ref "R9") (pin "1") (pinfunction "1_1") (pintype "passive"))
      (node (ref "X1") (pin "13") (pinfunction "13_13") (pintype "passive"))
    )
    (net (code "74") (name "SELT") (class "Default")
      (node (ref "C37") (pin "2") (pinfunction "2_2") (pintype "passive"))
      (node (ref "R1") (pin "2") (pinfunction "2_2") (pintype "passive"))
      (node (ref "R18") (pin "2") (pinfunction "2_2") (pintype "passive"))
      (node (ref "U1") (pin "11") (pinfunction "LE_11") (pintype "input"))
    )
    (net (code "75") (name "STRB") (class "Default")
      (node (ref "C40") (pin "2") (pinfunction "2_2") (pintype "passive"))
      (node (ref "R24") (pin "1") (pinfunction "1_1") (pintype "passive"))
      (node (ref "R4") (pin "2") (pinfunction "2_2") (pintype "passive"))
      (node (ref "U4") (pin "11") (pinfunction "LE_11") (pintype "input"))
    )
    (net (code "76") (name "WAIT") (class "Default")
      (node (ref "P5") (pin "4") (pinfunction "4_4") (pintype "passive"))
      (node (ref "R11") (pin "1") (pinfunction "1_1") (pintype "passive"))
      (node (ref "X1") (pin "11") (pinfunction "11_11") (pintype "passive"))
    )
    (net (code "77") (name "unconnected-(U7-LOW_VOLTAGE_LV-Pad6)") (class "Default")
      (node (ref "U7") (pin "6") (pinfunction "LOW_VOLTAGE_LV_6") (pintype "input"))
    )
    (net (code "78") (name "unconnected-(U7-OSC-Pad7)") (class "Default")
      (node (ref "U7") (pin "7") (pinfunction "OSC_7") (pintype "input"))
    )
    (net (code "79") (name "unconnected-(X1-Pad15)") (class "Default")
      (node (ref "X1") (pin "15") (pinfunction "15_15") (pintype "passive"))
    )
  )
)
